# SchemeGOST.net
KiCad netlist of a schematic drawn in Altium Designer
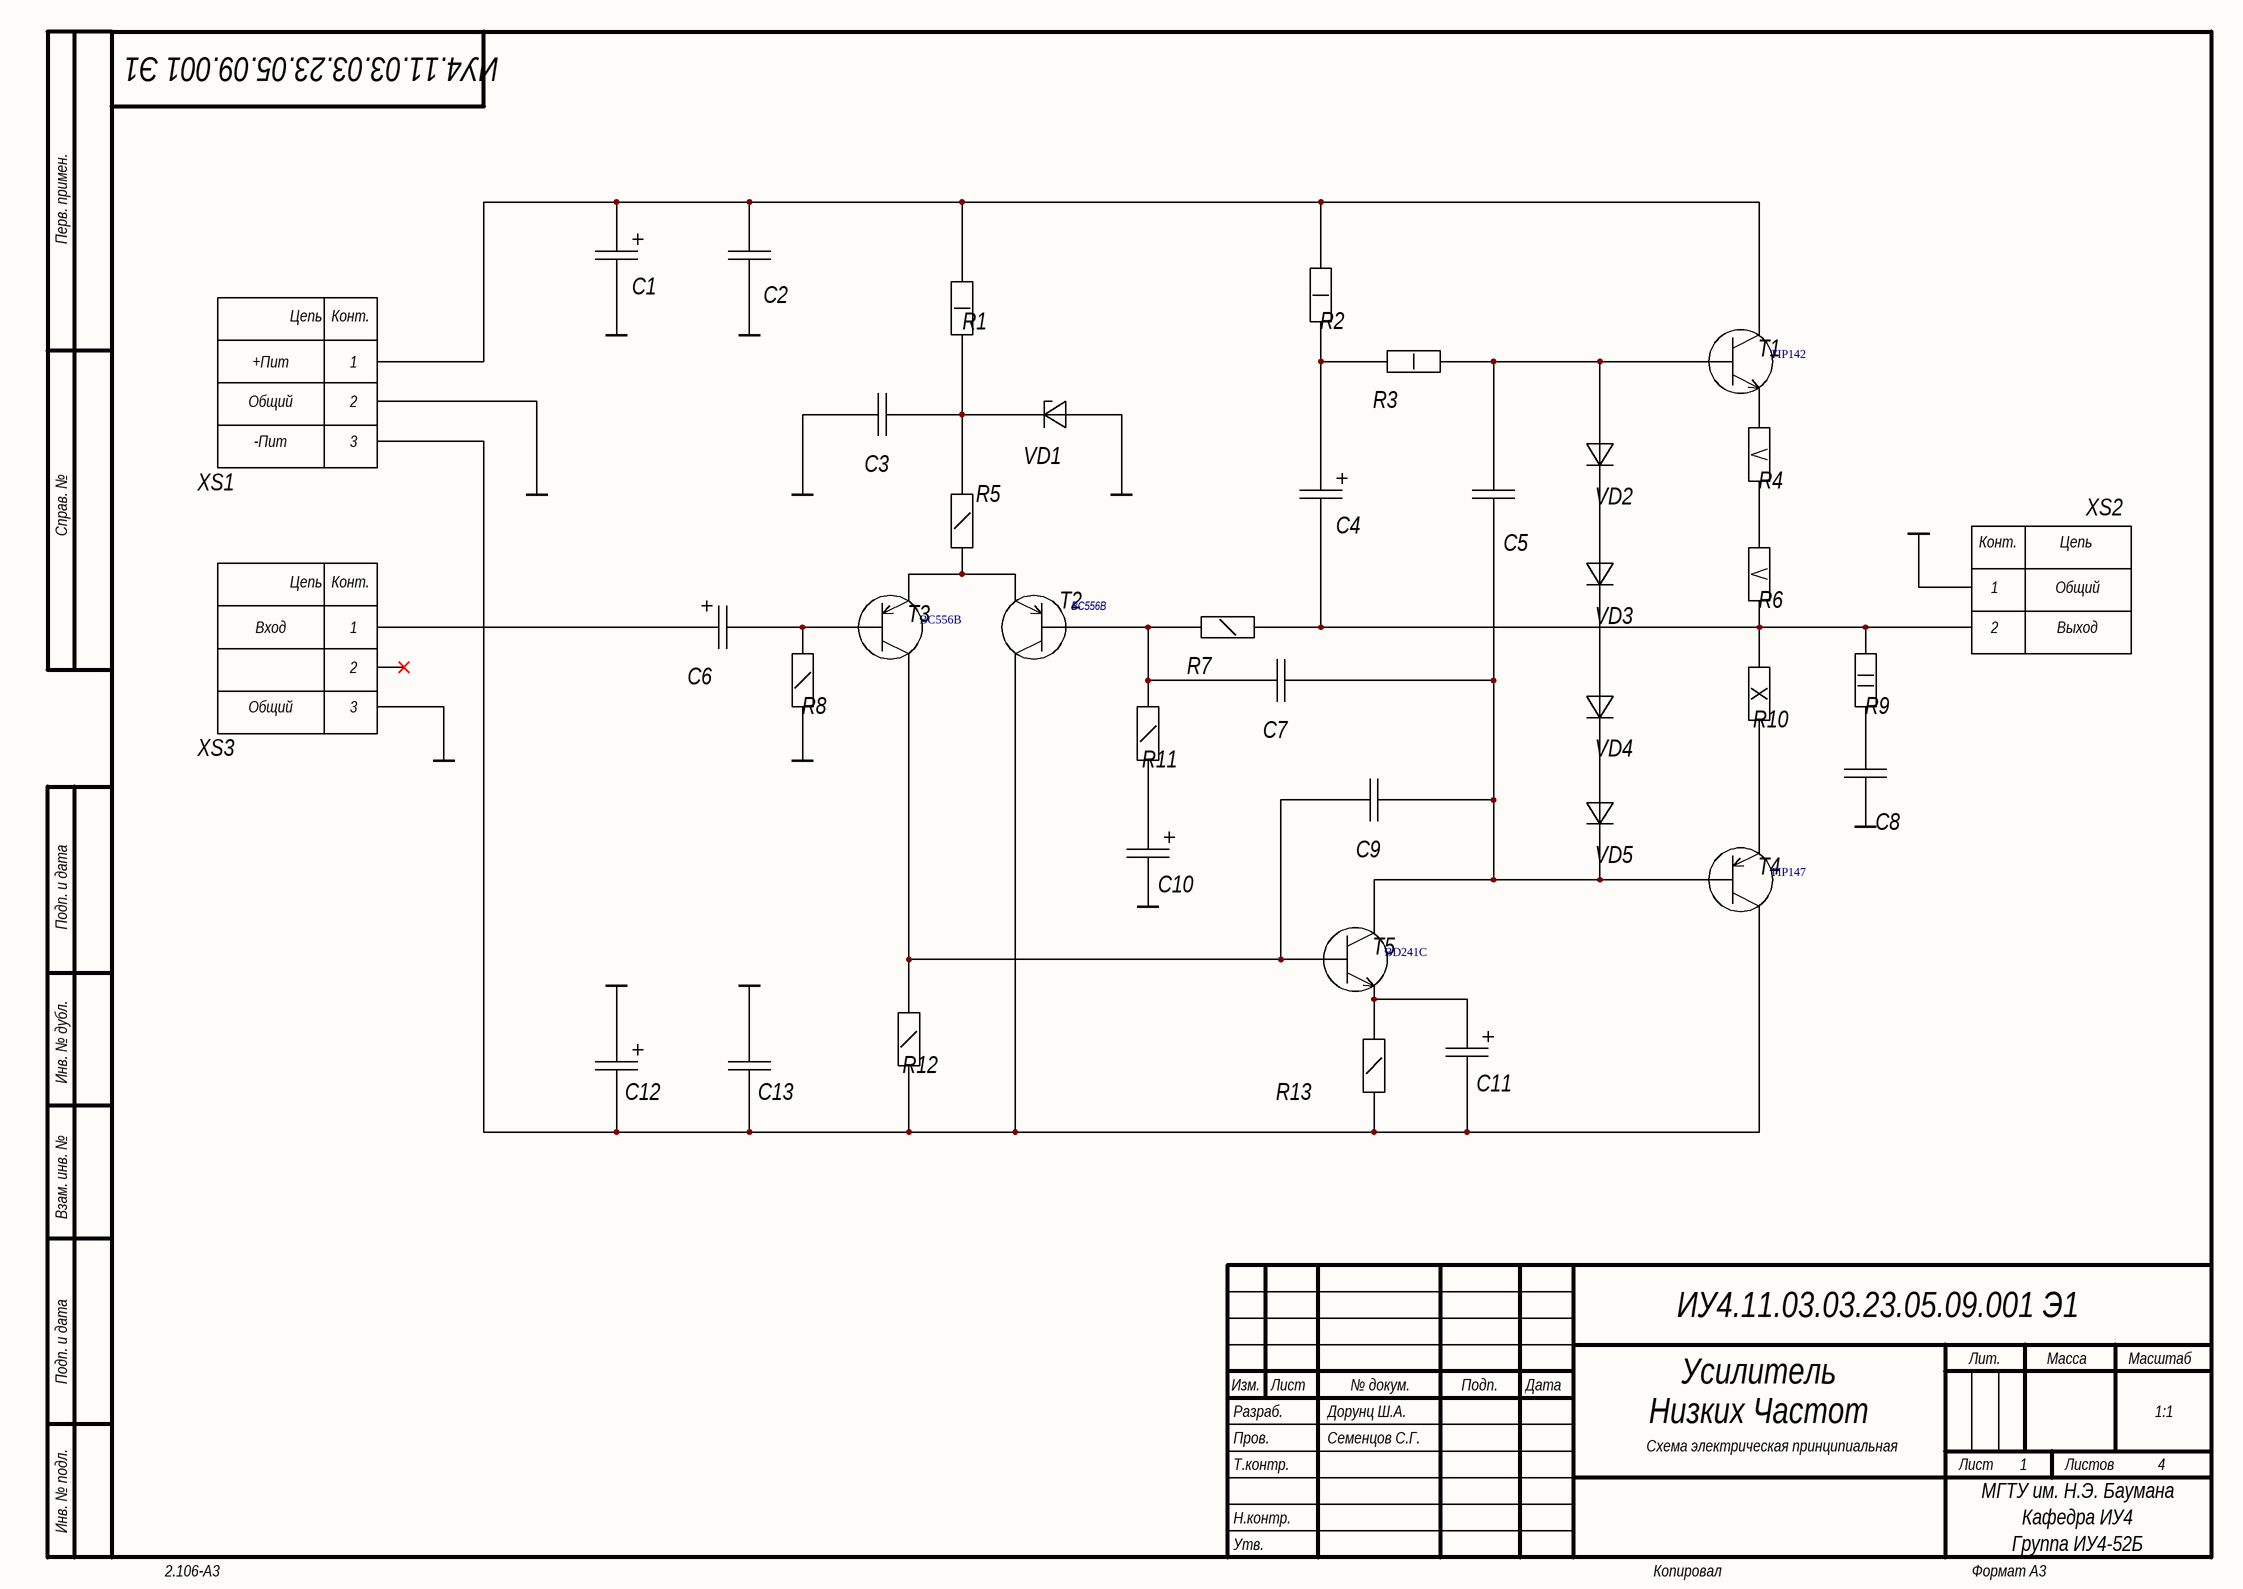
[diagram p0: SchemeGOST.SchDoc]

(export (version "E")
  (design (tool "Eeschema 10.0.6"))
  (components
    (comp (ref "C1")
      (value "220uF/100V")
      (footprint "Cap 220U/100V")
      (fields (field (name "PUBLISHER") "Andrew Danich"))
      (libsource (lib "Kursovaya") (part "Capacitor 220uF 100V"))
    )
    (comp (ref "C2")
      (value "1uF/63V")
      (footprint "Cap 1u/63V")
      (fields (field (name "PUBLISHER") "Andrew Danich"))
      (libsource (lib "Kursovaya") (part "Capacitor 1uF 63V"))
    )
    (comp (ref "C3")
      (value "220nF")
      (footprint "Cap 220nF")
      (fields (field (name "PUBLISHER") "Andrew Danich"))
      (libsource (lib "Kursovaya") (part "Capacitor 220nF"))
    )
    (comp (ref "C4")
      (value "220uF/50V")
      (footprint "Cap 220U/100V")
      (fields (field (name "PUBLISHER") "Andrew Danich"))
      (libsource (lib "Kursovaya") (part "Capacitor 220uF 50V"))
    )
    (comp (ref "C5")
      (value "470nF")
      (footprint "Cap 470n")
      (fields (field (name "PUBLISHER") "Andrew Danich"))
      (libsource (lib "Kursovaya") (part "Capacitor 470nF"))
    )
    (comp (ref "C6")
      (value "10uF/25V")
      (footprint "Cap 10u/25V")
      (fields (field (name "PUBLISHER") "Andrew Danich"))
      (libsource (lib "Kursovaya") (part "Capacitor 10uF 25V"))
    )
    (comp (ref "C7")
      (value "220pF")
      (footprint "Cap 220p")
      (fields (field (name "PUBLISHER") "Andrew Danich"))
      (libsource (lib "Kursovaya") (part "Capacitor 220pF"))
    )
    (comp (ref "C8")
      (value "100nF/100V")
      (footprint "Cap 100n/100V")
      (fields (field (name "PUBLISHER") "Andrew Danich"))
      (libsource (lib "Kursovaya") (part "Capacitor 100nF 100V"))
    )
    (comp (ref "C9")
      (value "100pF/100V")
      (footprint "Cap 100p")
      (fields (field (name "PUBLISHER") "Andrew Danich"))
      (libsource (lib "Kursovaya") (part "Capacitor 100pF 100V"))
    )
    (comp (ref "C10")
      (value "470uF/10V")
      (footprint "Cap 470u/10V")
      (fields (field (name "PUBLISHER") "Andrew Danich"))
      (libsource (lib "Kursovaya") (part "Capacitor 470uF 10V"))
    )
    (comp (ref "C11")
      (value "10uF/25V")
      (footprint "Cap 10u/25V")
      (fields (field (name "PUBLISHER") "Andrew Danich"))
      (libsource (lib "Kursovaya") (part "Capacitor 10uF 25V"))
    )
    (comp (ref "C12")
      (value "220uF/100V")
      (footprint "Cap 220U/100V")
      (fields (field (name "PUBLISHER") "Andrew Danich"))
      (libsource (lib "Kursovaya") (part "Capacitor 220uF 100V"))
    )
    (comp (ref "C13")
      (value "1uF/63V")
      (footprint "Cap 1u/63V")
      (fields (field (name "PUBLISHER") "Andrew Danich"))
      (libsource (lib "Kursovaya") (part "Capacitor 1uF 63V"))
    )
    (comp (ref "R1")
      (value "Resistor 1W")
      (footprint "Res 1W")
      (fields (field (name "PUBLISHER") "Andrew Danich"))
      (libsource (lib "Kursovaya") (part "Resistor 1W"))
    )
    (comp (ref "R2")
      (value "Resistor 1W")
      (footprint "Res 1W")
      (fields (field (name "PUBLISHER") "Andrew Danich"))
      (libsource (lib "Kursovaya") (part "Resistor 1W"))
    )
    (comp (ref "R3")
      (value "Resistor 1W")
      (footprint "Res 1W")
      (fields (field (name "PUBLISHER") "Andrew Danich"))
      (libsource (lib "Kursovaya") (part "Resistor 1W"))
    )
    (comp (ref "R4")
      (value "Resistor 5W")
      (footprint "Res 5W")
      (fields (field (name "PUBLISHER") "Andrew Danich"))
      (libsource (lib "Kursovaya") (part "Resistor 5W"))
    )
    (comp (ref "R5")
      (value "Resistor 0.25W")
      (footprint "Res 0.25W")
      (fields (field (name "PUBLISHER") "Andrew Danich"))
      (libsource (lib "Kursovaya") (part "Resistor 0.25W"))
    )
    (comp (ref "R6")
      (value "Resistor 5W")
      (footprint "Res 5W")
      (fields (field (name "PUBLISHER") "Andrew Danich"))
      (libsource (lib "Kursovaya") (part "Resistor 5W"))
    )
    (comp (ref "R7")
      (value "Resistor 0.25W")
      (footprint "Res 0.25W")
      (fields (field (name "PUBLISHER") "Andrew Danich"))
      (libsource (lib "Kursovaya") (part "Resistor 0.25W"))
    )
    (comp (ref "R8")
      (value "Resistor 0.25W")
      (footprint "Res 0.25W")
      (fields (field (name "PUBLISHER") "Andrew Danich"))
      (libsource (lib "Kursovaya") (part "Resistor 0.25W"))
    )
    (comp (ref "R9")
      (value "Resistor 2W")
      (footprint "Res 2W")
      (fields (field (name "PUBLISHER") "Andrew Danich"))
      (libsource (lib "Kursovaya") (part "Resistor 2W"))
    )
    (comp (ref "R10")
      (value "Resistor 10W")
      (footprint "Res 10W")
      (fields (field (name "PUBLISHER") "Andrew Danich"))
      (libsource (lib "Kursovaya") (part "Resistor 10W"))
    )
    (comp (ref "R11")
      (value "Resistor 0.25W")
      (footprint "Res 0.25W")
      (fields (field (name "PUBLISHER") "Andrew Danich"))
      (libsource (lib "Kursovaya") (part "Resistor 0.25W"))
    )
    (comp (ref "R12")
      (value "Resistor 0.25W")
      (footprint "Res 0.25W")
      (fields (field (name "PUBLISHER") "Andrew Danich"))
      (libsource (lib "Kursovaya") (part "Resistor 0.25W"))
    )
    (comp (ref "R13")
      (value "Resistor 0.25W")
      (footprint "Res 0.25W")
      (fields (field (name "PUBLISHER") "Andrew Danich"))
      (libsource (lib "Kursovaya") (part "Resistor 0.25W"))
    )
    (comp (ref "T1") (value "TIP142") (footprint "TO-247") (libsource (lib "Kursovaya") (part "TIP142")))
    (comp (ref "T2") (value "BC556B") (footprint "TO-92-A") (libsource (lib "Kursovaya") (part "BC556B")))
    (comp (ref "T3") (value "BC556B") (footprint "TO-92-A") (libsource (lib "Kursovaya") (part "BC556B")))
    (comp (ref "T4") (value "TIP147") (footprint "TO-247") (libsource (lib "Kursovaya") (part "TIP147")))
    (comp (ref "T5") (value "BD241C") (footprint "TO-220") (libsource (lib "Kursovaya") (part "BD241C")))
    (comp (ref "VD1")
      (value "ZPD12")
      (footprint "DO-35")
      (fields (field (name "PUBLISHER") "Andrew Danich"))
      (libsource (lib "Kursovaya") (part "ZPD12"))
    )
    (comp (ref "VD2")
      (value "Diode 1N4001")
      (footprint "DO-41")
      (fields (field (name "PUBLISHER") "Andrew Danich"))
      (libsource (lib "Kursovaya") (part "Diode 1N4001"))
    )
    (comp (ref "VD3")
      (value "Diode 1N4001")
      (footprint "DO-41")
      (fields (field (name "PUBLISHER") "Andrew Danich"))
      (libsource (lib "Kursovaya") (part "Diode 1N4001"))
    )
    (comp (ref "VD4")
      (value "Diode 1N4001")
      (footprint "DO-41")
      (fields (field (name "PUBLISHER") "Andrew Danich"))
      (libsource (lib "Kursovaya") (part "Diode 1N4001"))
    )
    (comp (ref "VD5")
      (value "Diode 1N4001")
      (footprint "DO-41")
      (fields (field (name "PUBLISHER") "Andrew Danich"))
      (libsource (lib "Kursovaya") (part "Diode 1N4001"))
    )
    (comp (ref "XS1")
      (value "Connector 15EDGRC-3.81-03P")
      (footprint "15EDGRC-3.81-03P")
      (libsource (lib "Kursovaya") (part "Connector 15EDGRC-3.81-03P"))
    )
    (comp (ref "XS2")
      (value "Connector 15EDGRC-3.81-02P")
      (footprint "15EDGRC-3.81-02P")
      (libsource (lib "Kursovaya") (part "Connector 15EDGRC-3.81-02P"))
    )
    (comp (ref "XS3")
      (value "Connector ST-025")
      (footprint "ST-025")
      (libsource (lib "Kursovaya") (part "Connector ST-025"))
    )
  )
  (nets
    (net (code "1") (name "GND") (class "Default")
      (node (ref "C1") (pin "2") (pinfunction "2_2") (pintype "passive"))
      (node (ref "C10") (pin "2") (pinfunction "2_2") (pintype "passive"))
      (node (ref "C12") (pin "1") (pinfunction "1_1") (pintype "passive"))
      (node (ref "C13") (pin "1") (pinfunction "1_1") (pintype "passive"))
      (node (ref "C2") (pin "1") (pinfunction "1_1") (pintype "passive"))
      (node (ref "C3") (pin "2") (pinfunction "2_2") (pintype "passive"))
      (node (ref "C8") (pin "1") (pinfunction "1_1") (pintype "passive"))
      (node (ref "R8") (pin "1") (pinfunction "1_1") (pintype "passive"))
      (node (ref "VD1") (pin "1") (pinfunction "А_1") (pintype "passive"))
      (node (ref "XS1") (pin "2") (pinfunction "2_2") (pintype "passive"))
      (node (ref "XS2") (pin "1") (pinfunction "1_1") (pintype "passive"))
      (node (ref "XS3") (pin "3") (pinfunction "3_3") (pintype "passive"))
    )
    (net (code "2") (name "Net-(C4-Pad1)") (class "Default")
      (node (ref "C4") (pin "1") (pinfunction "1_1") (pintype "passive"))
      (node (ref "R2") (pin "1") (pinfunction "1_1") (pintype "passive"))
      (node (ref "R3") (pin "1") (pinfunction "1_1") (pintype "passive"))
    )
    (net (code "3") (name "Net-(C4-Pad2)") (class "Default")
      (node (ref "C4") (pin "2") (pinfunction "2_2") (pintype "passive"))
      (node (ref "R10") (pin "2") (pinfunction "2_2") (pintype "passive"))
      (node (ref "R6") (pin "2") (pinfunction "2_2") (pintype "passive"))
      (node (ref "R7") (pin "2") (pinfunction "2_2") (pintype "passive"))
      (node (ref "R9") (pin "2") (pinfunction "2_2") (pintype "passive"))
      (node (ref "XS2") (pin "2") (pinfunction "2_2") (pintype "passive"))
    )
    (net (code "4") (name "Net-(C6-Pad1)") (class "Default")
      (node (ref "C6") (pin "1") (pinfunction "1_1") (pintype "passive"))
      (node (ref "XS3") (pin "1") (pinfunction "1_1") (pintype "passive"))
    )
    (net (code "5") (name "Net-(C8-Pad2)") (class "Default")
      (node (ref "C8") (pin "2") (pinfunction "2_2") (pintype "passive"))
      (node (ref "R9") (pin "1") (pinfunction "1_1") (pintype "passive"))
    )
    (net (code "6") (name "Net-(C10-Pad1)") (class "Default")
      (node (ref "C10") (pin "1") (pinfunction "1_1") (pintype "passive"))
      (node (ref "R11") (pin "1") (pinfunction "1_1") (pintype "passive"))
    )
    (net (code "7") (name "Net-(R4-Pad2)") (class "Default")
      (node (ref "R4") (pin "2") (pinfunction "2_2") (pintype "passive"))
      (node (ref "R6") (pin "1") (pinfunction "1_1") (pintype "passive"))
    )
    (net (code "8") (name "Net-(T1-B)") (class "Default")
      (node (ref "C5") (pin "2") (pinfunction "2_2") (pintype "passive"))
      (node (ref "R3") (pin "2") (pinfunction "2_2") (pintype "passive"))
      (node (ref "T1") (pin "1") (pinfunction "B_1") (pintype "passive"))
      (node (ref "VD2") (pin "1") (pinfunction "А_1") (pintype "passive"))
    )
    (net (code "9") (name "Net-(T1-C)") (class "Default")
      (node (ref "C1") (pin "1") (pinfunction "1_1") (pintype "passive"))
      (node (ref "C2") (pin "2") (pinfunction "2_2") (pintype "passive"))
      (node (ref "R1") (pin "2") (pinfunction "2_2") (pintype "passive"))
      (node (ref "R2") (pin "2") (pinfunction "2_2") (pintype "passive"))
      (node (ref "T1") (pin "2") (pinfunction "C_2") (pintype "passive"))
      (node (ref "XS1") (pin "1") (pinfunction "1_1") (pintype "passive"))
    )
    (net (code "10") (name "Net-(T1-E)") (class "Default")
      (node (ref "R4") (pin "1") (pinfunction "1_1") (pintype "passive"))
      (node (ref "T1") (pin "3") (pinfunction "E_3") (pintype "passive"))
    )
    (net (code "11") (name "Net-(T2-B)") (class "Default")
      (node (ref "C7") (pin "1") (pinfunction "1_1") (pintype "passive"))
      (node (ref "R11") (pin "2") (pinfunction "2_2") (pintype "passive"))
      (node (ref "R7") (pin "1") (pinfunction "1_1") (pintype "passive"))
      (node (ref "T2") (pin "2") (pinfunction "B_2") (pintype "passive"))
    )
    (net (code "12") (name "Net-(T2-C)") (class "Default")
      (node (ref "C11") (pin "2") (pinfunction "2_2") (pintype "passive"))
      (node (ref "C12") (pin "2") (pinfunction "2_2") (pintype "passive"))
      (node (ref "C13") (pin "2") (pinfunction "2_2") (pintype "passive"))
      (node (ref "R12") (pin "1") (pinfunction "1_1") (pintype "passive"))
      (node (ref "R13") (pin "1") (pinfunction "1_1") (pintype "passive"))
      (node (ref "T2") (pin "1") (pinfunction "C_1") (pintype "passive"))
      (node (ref "T4") (pin "2") (pinfunction "C_2") (pintype "passive"))
      (node (ref "XS1") (pin "3") (pinfunction "3_3") (pintype "passive"))
    )
    (net (code "13") (name "Net-(T2-E)") (class "Default")
      (node (ref "R5") (pin "1") (pinfunction "1_1") (pintype "passive"))
      (node (ref "T2") (pin "3") (pinfunction "E_3") (pintype "passive"))
      (node (ref "T3") (pin "3") (pinfunction "E_3") (pintype "passive"))
    )
    (net (code "14") (name "Net-(T3-B)") (class "Default")
      (node (ref "C6") (pin "2") (pinfunction "2_2") (pintype "passive"))
      (node (ref "R8") (pin "2") (pinfunction "2_2") (pintype "passive"))
      (node (ref "T3") (pin "2") (pinfunction "B_2") (pintype "passive"))
    )
    (net (code "15") (name "Net-(T3-C)") (class "Default")
      (node (ref "C9") (pin "1") (pinfunction "1_1") (pintype "passive"))
      (node (ref "R12") (pin "2") (pinfunction "2_2") (pintype "passive"))
      (node (ref "T3") (pin "1") (pinfunction "C_1") (pintype "passive"))
      (node (ref "T5") (pin "1") (pinfunction "B_1") (pintype "passive"))
    )
    (net (code "16") (name "Net-(T4-B)") (class "Default")
      (node (ref "C5") (pin "1") (pinfunction "1_1") (pintype "passive"))
      (node (ref "C7") (pin "2") (pinfunction "2_2") (pintype "passive"))
      (node (ref "C9") (pin "2") (pinfunction "2_2") (pintype "passive"))
      (node (ref "T4") (pin "1") (pinfunction "B_1") (pintype "passive"))
      (node (ref "T5") (pin "2") (pinfunction "C_2") (pintype "passive"))
      (node (ref "VD5") (pin "2") (pinfunction "К_2") (pintype "passive"))
    )
    (net (code "17") (name "Net-(T4-E)") (class "Default")
      (node (ref "R10") (pin "1") (pinfunction "1_1") (pintype "passive"))
      (node (ref "T4") (pin "3") (pinfunction "E_3") (pintype "passive"))
    )
    (net (code "18") (name "Net-(T5-E)") (class "Default")
      (node (ref "C11") (pin "1") (pinfunction "1_1") (pintype "passive"))
      (node (ref "R13") (pin "2") (pinfunction "2_2") (pintype "passive"))
      (node (ref "T5") (pin "3") (pinfunction "E_3") (pintype "passive"))
    )
    (net (code "19") (name "Net-(VD1-К)") (class "Default")
      (node (ref "C3") (pin "1") (pinfunction "1_1") (pintype "passive"))
      (node (ref "R1") (pin "1") (pinfunction "1_1") (pintype "passive"))
      (node (ref "R5") (pin "2") (pinfunction "2_2") (pintype "passive"))
      (node (ref "VD1") (pin "2") (pinfunction "К_2") (pintype "passive"))
    )
    (net (code "20") (name "Net-(VD2-К)") (class "Default")
      (node (ref "VD2") (pin "2") (pinfunction "К_2") (pintype "passive"))
      (node (ref "VD3") (pin "1") (pinfunction "А_1") (pintype "passive"))
    )
    (net (code "21") (name "Net-(VD3-К)") (class "Default")
      (node (ref "VD3") (pin "2") (pinfunction "К_2") (pintype "passive"))
      (node (ref "VD4") (pin "1") (pinfunction "А_1") (pintype "passive"))
    )
    (net (code "22") (name "Net-(VD4-К)") (class "Default")
      (node (ref "VD4") (pin "2") (pinfunction "К_2") (pintype "passive"))
      (node (ref "VD5") (pin "1") (pinfunction "А_1") (pintype "passive"))
    )
    (net (code "23") (name "unconnected-(XS3-Pad2)") (class "Default")
      (node (ref "XS3") (pin "2") (pinfunction "2_2") (pintype "passive+no_connect"))
    )
  )
)
